# ALU_XOR.net
KiCad netlist of a schematic drawn in Altium Designer
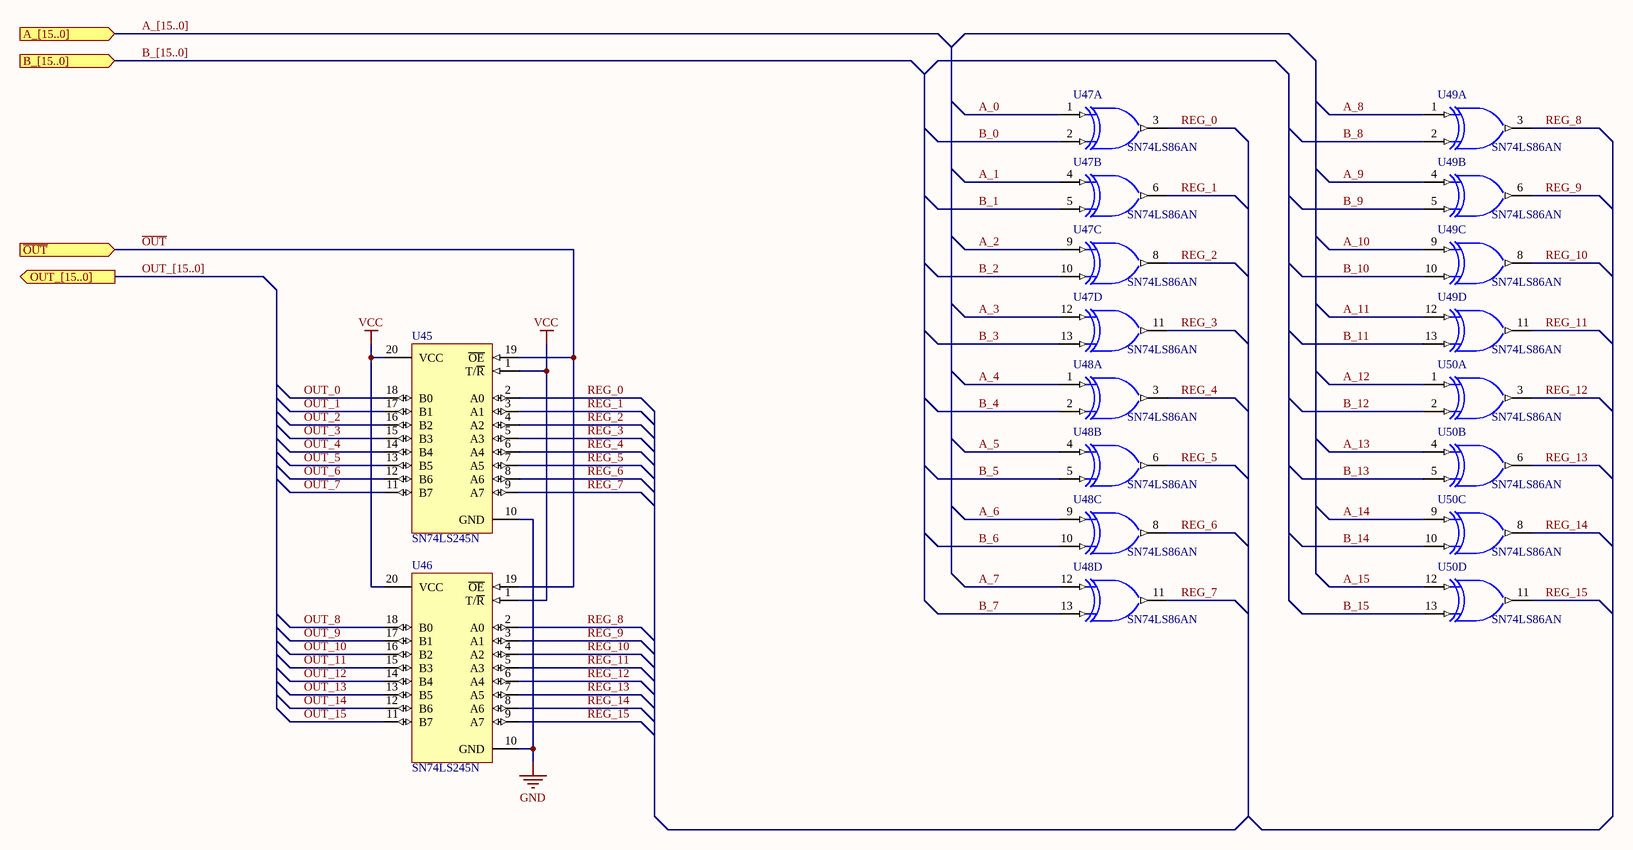
[diagram p0: ALU_XOR.SchDoc]

(export (version "E")
  (design (tool "Eeschema 10.0.6"))
  (components
    (comp (ref "U45")
      (value "SN74LS245N")
      (footprint "N020")
      (description "Octal Bus Transceiver with 3-State Outputs")
      (fields (field (name "PUBLISHER") "Altium Limited"))
      (libsource (lib "TI Interface 8-Bit Line Transceiver") (part "SN74LS245N"))
    )
    (comp (ref "U46")
      (value "SN74LS245N")
      (footprint "N020")
      (description "Octal Bus Transceiver with 3-State Outputs")
      (fields (field (name "PUBLISHER") "Altium Limited"))
      (libsource (lib "TI Interface 8-Bit Line Transceiver") (part "SN74LS245N"))
    )
    (comp (ref "U47")
      (value "SN74LS86AN")
      (footprint "N014")
      (description "Quadruple 2-Input Exclusive-OR Gate")
      (fields (field (name "PUBLISHER") "Altium Limited"))
      (libsource (lib "TI Logic Gate 2") (part "SN74LS86AN"))
    )
    (comp (ref "U48")
      (value "SN74LS86AN")
      (footprint "N014")
      (description "Quadruple 2-Input Exclusive-OR Gate")
      (fields (field (name "PUBLISHER") "Altium Limited"))
      (libsource (lib "TI Logic Gate 2") (part "SN74LS86AN"))
    )
    (comp (ref "U49")
      (value "SN74LS86AN")
      (footprint "N014")
      (description "Quadruple 2-Input Exclusive-OR Gate")
      (fields (field (name "PUBLISHER") "Altium Limited"))
      (libsource (lib "TI Logic Gate 2") (part "SN74LS86AN"))
    )
    (comp (ref "U50")
      (value "SN74LS86AN")
      (footprint "N014")
      (description "Quadruple 2-Input Exclusive-OR Gate")
      (fields (field (name "PUBLISHER") "Altium Limited"))
      (libsource (lib "TI Logic Gate 2") (part "SN74LS86AN"))
    )
  )
  (nets
    (net (code "1") (name "/A_0") (class "Default")
      (node (ref "U47") (pin "1") (pinfunction "A_1") (pintype "input"))
    )
    (net (code "2") (name "/A_1") (class "Default")
      (node (ref "U47") (pin "4") (pinfunction "A_4") (pintype "input"))
    )
    (net (code "3") (name "/A_2") (class "Default")
      (node (ref "U47") (pin "9") (pinfunction "A_9") (pintype "input"))
    )
    (net (code "4") (name "/A_3") (class "Default")
      (node (ref "U47") (pin "12") (pinfunction "A_12") (pintype "input"))
    )
    (net (code "5") (name "/A_4") (class "Default")
      (node (ref "U48") (pin "1") (pinfunction "A_1") (pintype "input"))
    )
    (net (code "6") (name "/A_5") (class "Default")
      (node (ref "U48") (pin "4") (pinfunction "A_4") (pintype "input"))
    )
    (net (code "7") (name "/A_6") (class "Default")
      (node (ref "U48") (pin "9") (pinfunction "A_9") (pintype "input"))
    )
    (net (code "8") (name "/A_7") (class "Default")
      (node (ref "U48") (pin "12") (pinfunction "A_12") (pintype "input"))
    )
    (net (code "9") (name "/A_8") (class "Default")
      (node (ref "U49") (pin "1") (pinfunction "A_1") (pintype "input"))
    )
    (net (code "10") (name "/A_9") (class "Default")
      (node (ref "U49") (pin "4") (pinfunction "A_4") (pintype "input"))
    )
    (net (code "11") (name "/A_10") (class "Default")
      (node (ref "U49") (pin "9") (pinfunction "A_9") (pintype "input"))
    )
    (net (code "12") (name "/A_11") (class "Default")
      (node (ref "U49") (pin "12") (pinfunction "A_12") (pintype "input"))
    )
    (net (code "13") (name "/A_12") (class "Default")
      (node (ref "U50") (pin "1") (pinfunction "A_1") (pintype "input"))
    )
    (net (code "14") (name "/A_13") (class "Default")
      (node (ref "U50") (pin "4") (pinfunction "A_4") (pintype "input"))
    )
    (net (code "15") (name "/A_14") (class "Default")
      (node (ref "U50") (pin "9") (pinfunction "A_9") (pintype "input"))
    )
    (net (code "16") (name "/A_15") (class "Default")
      (node (ref "U50") (pin "12") (pinfunction "A_12") (pintype "input"))
    )
    (net (code "18") (name "/B_0") (class "Default")
      (node (ref "U47") (pin "2") (pinfunction "B_2") (pintype "input"))
    )
    (net (code "19") (name "/B_1") (class "Default")
      (node (ref "U47") (pin "5") (pinfunction "B_5") (pintype "input"))
    )
    (net (code "20") (name "/B_2") (class "Default")
      (node (ref "U47") (pin "10") (pinfunction "B_10") (pintype "input"))
    )
    (net (code "21") (name "/B_3") (class "Default")
      (node (ref "U47") (pin "13") (pinfunction "B_13") (pintype "input"))
    )
    (net (code "22") (name "/B_4") (class "Default")
      (node (ref "U48") (pin "2") (pinfunction "B_2") (pintype "input"))
    )
    (net (code "23") (name "/B_5") (class "Default")
      (node (ref "U48") (pin "5") (pinfunction "B_5") (pintype "input"))
    )
    (net (code "24") (name "/B_6") (class "Default")
      (node (ref "U48") (pin "10") (pinfunction "B_10") (pintype "input"))
    )
    (net (code "25") (name "/B_7") (class "Default")
      (node (ref "U48") (pin "13") (pinfunction "B_13") (pintype "input"))
    )
    (net (code "26") (name "/B_8") (class "Default")
      (node (ref "U49") (pin "2") (pinfunction "B_2") (pintype "input"))
    )
    (net (code "27") (name "/B_9") (class "Default")
      (node (ref "U49") (pin "5") (pinfunction "B_5") (pintype "input"))
    )
    (net (code "28") (name "/B_10") (class "Default")
      (node (ref "U49") (pin "10") (pinfunction "B_10") (pintype "input"))
    )
    (net (code "29") (name "/B_11") (class "Default")
      (node (ref "U49") (pin "13") (pinfunction "B_13") (pintype "input"))
    )
    (net (code "30") (name "/B_12") (class "Default")
      (node (ref "U50") (pin "2") (pinfunction "B_2") (pintype "input"))
    )
    (net (code "31") (name "/B_13") (class "Default")
      (node (ref "U50") (pin "5") (pinfunction "B_5") (pintype "input"))
    )
    (net (code "32") (name "/B_14") (class "Default")
      (node (ref "U50") (pin "10") (pinfunction "B_10") (pintype "input"))
    )
    (net (code "33") (name "/B_15") (class "Default")
      (node (ref "U50") (pin "13") (pinfunction "B_13") (pintype "input"))
    )
    (net (code "35") (name "/OUT_0") (class "Default")
      (node (ref "U45") (pin "18") (pinfunction "B0_18") (pintype "bidirectional"))
    )
    (net (code "36") (name "/OUT_1") (class "Default")
      (node (ref "U45") (pin "17") (pinfunction "B1_17") (pintype "bidirectional"))
    )
    (net (code "37") (name "/OUT_2") (class "Default")
      (node (ref "U45") (pin "16") (pinfunction "B2_16") (pintype "bidirectional"))
    )
    (net (code "38") (name "/OUT_3") (class "Default")
      (node (ref "U45") (pin "15") (pinfunction "B3_15") (pintype "bidirectional"))
    )
    (net (code "39") (name "/OUT_4") (class "Default")
      (node (ref "U45") (pin "14") (pinfunction "B4_14") (pintype "bidirectional"))
    )
    (net (code "40") (name "/OUT_5") (class "Default")
      (node (ref "U45") (pin "13") (pinfunction "B5_13") (pintype "bidirectional"))
    )
    (net (code "41") (name "/OUT_6") (class "Default")
      (node (ref "U45") (pin "12") (pinfunction "B6_12") (pintype "bidirectional"))
    )
    (net (code "42") (name "/OUT_7") (class "Default")
      (node (ref "U45") (pin "11") (pinfunction "B7_11") (pintype "bidirectional"))
    )
    (net (code "43") (name "/OUT_8") (class "Default")
      (node (ref "U46") (pin "18") (pinfunction "B0_18") (pintype "bidirectional"))
    )
    (net (code "44") (name "/OUT_9") (class "Default")
      (node (ref "U46") (pin "17") (pinfunction "B1_17") (pintype "bidirectional"))
    )
    (net (code "45") (name "/OUT_10") (class "Default")
      (node (ref "U46") (pin "16") (pinfunction "B2_16") (pintype "bidirectional"))
    )
    (net (code "46") (name "/OUT_11") (class "Default")
      (node (ref "U46") (pin "15") (pinfunction "B3_15") (pintype "bidirectional"))
    )
    (net (code "47") (name "/OUT_12") (class "Default")
      (node (ref "U46") (pin "14") (pinfunction "B4_14") (pintype "bidirectional"))
    )
    (net (code "48") (name "/OUT_13") (class "Default")
      (node (ref "U46") (pin "13") (pinfunction "B5_13") (pintype "bidirectional"))
    )
    (net (code "49") (name "/OUT_14") (class "Default")
      (node (ref "U46") (pin "12") (pinfunction "B6_12") (pintype "bidirectional"))
    )
    (net (code "50") (name "/OUT_15") (class "Default")
      (node (ref "U46") (pin "11") (pinfunction "B7_11") (pintype "bidirectional"))
    )
    (net (code "52") (name "/REG_0") (class "Default")
      (node (ref "U45") (pin "2") (pinfunction "A0_2") (pintype "bidirectional"))
      (node (ref "U47") (pin "3") (pinfunction "Y_3") (pintype "output"))
    )
    (net (code "53") (name "/REG_1") (class "Default")
      (node (ref "U45") (pin "3") (pinfunction "A1_3") (pintype "bidirectional"))
      (node (ref "U47") (pin "6") (pinfunction "Y_6") (pintype "output"))
    )
    (net (code "54") (name "/REG_2") (class "Default")
      (node (ref "U45") (pin "4") (pinfunction "A2_4") (pintype "bidirectional"))
      (node (ref "U47") (pin "8") (pinfunction "Y_8") (pintype "output"))
    )
    (net (code "55") (name "/REG_3") (class "Default")
      (node (ref "U45") (pin "5") (pinfunction "A3_5") (pintype "bidirectional"))
      (node (ref "U47") (pin "11") (pinfunction "Y_11") (pintype "output"))
    )
    (net (code "56") (name "/REG_4") (class "Default")
      (node (ref "U45") (pin "6") (pinfunction "A4_6") (pintype "bidirectional"))
      (node (ref "U48") (pin "3") (pinfunction "Y_3") (pintype "output"))
    )
    (net (code "57") (name "/REG_5") (class "Default")
      (node (ref "U45") (pin "7") (pinfunction "A5_7") (pintype "bidirectional"))
      (node (ref "U48") (pin "6") (pinfunction "Y_6") (pintype "output"))
    )
    (net (code "58") (name "/REG_6") (class "Default")
      (node (ref "U45") (pin "8") (pinfunction "A6_8") (pintype "bidirectional"))
      (node (ref "U48") (pin "8") (pinfunction "Y_8") (pintype "output"))
    )
    (net (code "59") (name "/REG_7") (class "Default")
      (node (ref "U45") (pin "9") (pinfunction "A7_9") (pintype "bidirectional"))
      (node (ref "U48") (pin "11") (pinfunction "Y_11") (pintype "output"))
    )
    (net (code "60") (name "/REG_8") (class "Default")
      (node (ref "U46") (pin "2") (pinfunction "A0_2") (pintype "bidirectional"))
      (node (ref "U49") (pin "3") (pinfunction "Y_3") (pintype "output"))
    )
    (net (code "61") (name "/REG_9") (class "Default")
      (node (ref "U46") (pin "3") (pinfunction "A1_3") (pintype "bidirectional"))
      (node (ref "U49") (pin "6") (pinfunction "Y_6") (pintype "output"))
    )
    (net (code "62") (name "/REG_10") (class "Default")
      (node (ref "U46") (pin "4") (pinfunction "A2_4") (pintype "bidirectional"))
      (node (ref "U49") (pin "8") (pinfunction "Y_8") (pintype "output"))
    )
    (net (code "63") (name "/REG_11") (class "Default")
      (node (ref "U46") (pin "5") (pinfunction "A3_5") (pintype "bidirectional"))
      (node (ref "U49") (pin "11") (pinfunction "Y_11") (pintype "output"))
    )
    (net (code "64") (name "/REG_12") (class "Default")
      (node (ref "U46") (pin "6") (pinfunction "A4_6") (pintype "bidirectional"))
      (node (ref "U50") (pin "3") (pinfunction "Y_3") (pintype "output"))
    )
    (net (code "65") (name "/REG_13") (class "Default")
      (node (ref "U46") (pin "7") (pinfunction "A5_7") (pintype "bidirectional"))
      (node (ref "U50") (pin "6") (pinfunction "Y_6") (pintype "output"))
    )
    (net (code "66") (name "/REG_14") (class "Default")
      (node (ref "U46") (pin "8") (pinfunction "A6_8") (pintype "bidirectional"))
      (node (ref "U50") (pin "8") (pinfunction "Y_8") (pintype "output"))
    )
    (net (code "67") (name "/REG_15") (class "Default")
      (node (ref "U46") (pin "9") (pinfunction "A7_9") (pintype "bidirectional"))
      (node (ref "U50") (pin "11") (pinfunction "Y_11") (pintype "output"))
    )
    (net (code "68") (name "/~{OUT}") (class "Default")
      (node (ref "U45") (pin "19") (pinfunction "~{OE}_19") (pintype "input"))
      (node (ref "U46") (pin "19") (pinfunction "~{OE}_19") (pintype "input"))
    )
    (net (code "69") (name "GND") (class "Default")
      (node (ref "U45") (pin "10") (pinfunction "GND_10") (pintype "power_in"))
      (node (ref "U46") (pin "10") (pinfunction "GND_10") (pintype "power_in"))
      (node (ref "U47") (pin "7") (pinfunction "GND_7") (pintype "power_in"))
      (node (ref "U48") (pin "7") (pinfunction "GND_7") (pintype "power_in"))
      (node (ref "U49") (pin "7") (pinfunction "GND_7") (pintype "power_in"))
      (node (ref "U50") (pin "7") (pinfunction "GND_7") (pintype "power_in"))
    )
    (net (code "70") (name "VCC") (class "Default")
      (node (ref "U45") (pin "1") (pinfunction "T/~{R}_1") (pintype "input"))
      (node (ref "U45") (pin "20") (pinfunction "VCC_20") (pintype "power_in"))
      (node (ref "U46") (pin "1") (pinfunction "T/~{R}_1") (pintype "input"))
      (node (ref "U46") (pin "20") (pinfunction "VCC_20") (pintype "power_in"))
      (node (ref "U47") (pin "14") (pinfunction "VCC_14") (pintype "power_in"))
      (node (ref "U48") (pin "14") (pinfunction "VCC_14") (pintype "power_in"))
      (node (ref "U49") (pin "14") (pinfunction "VCC_14") (pintype "power_in"))
      (node (ref "U50") (pin "14") (pinfunction "VCC_14") (pintype "power_in"))
    )
  )
)
